# fadic.net
KiCad netlist of a schematic drawn in EAGLE
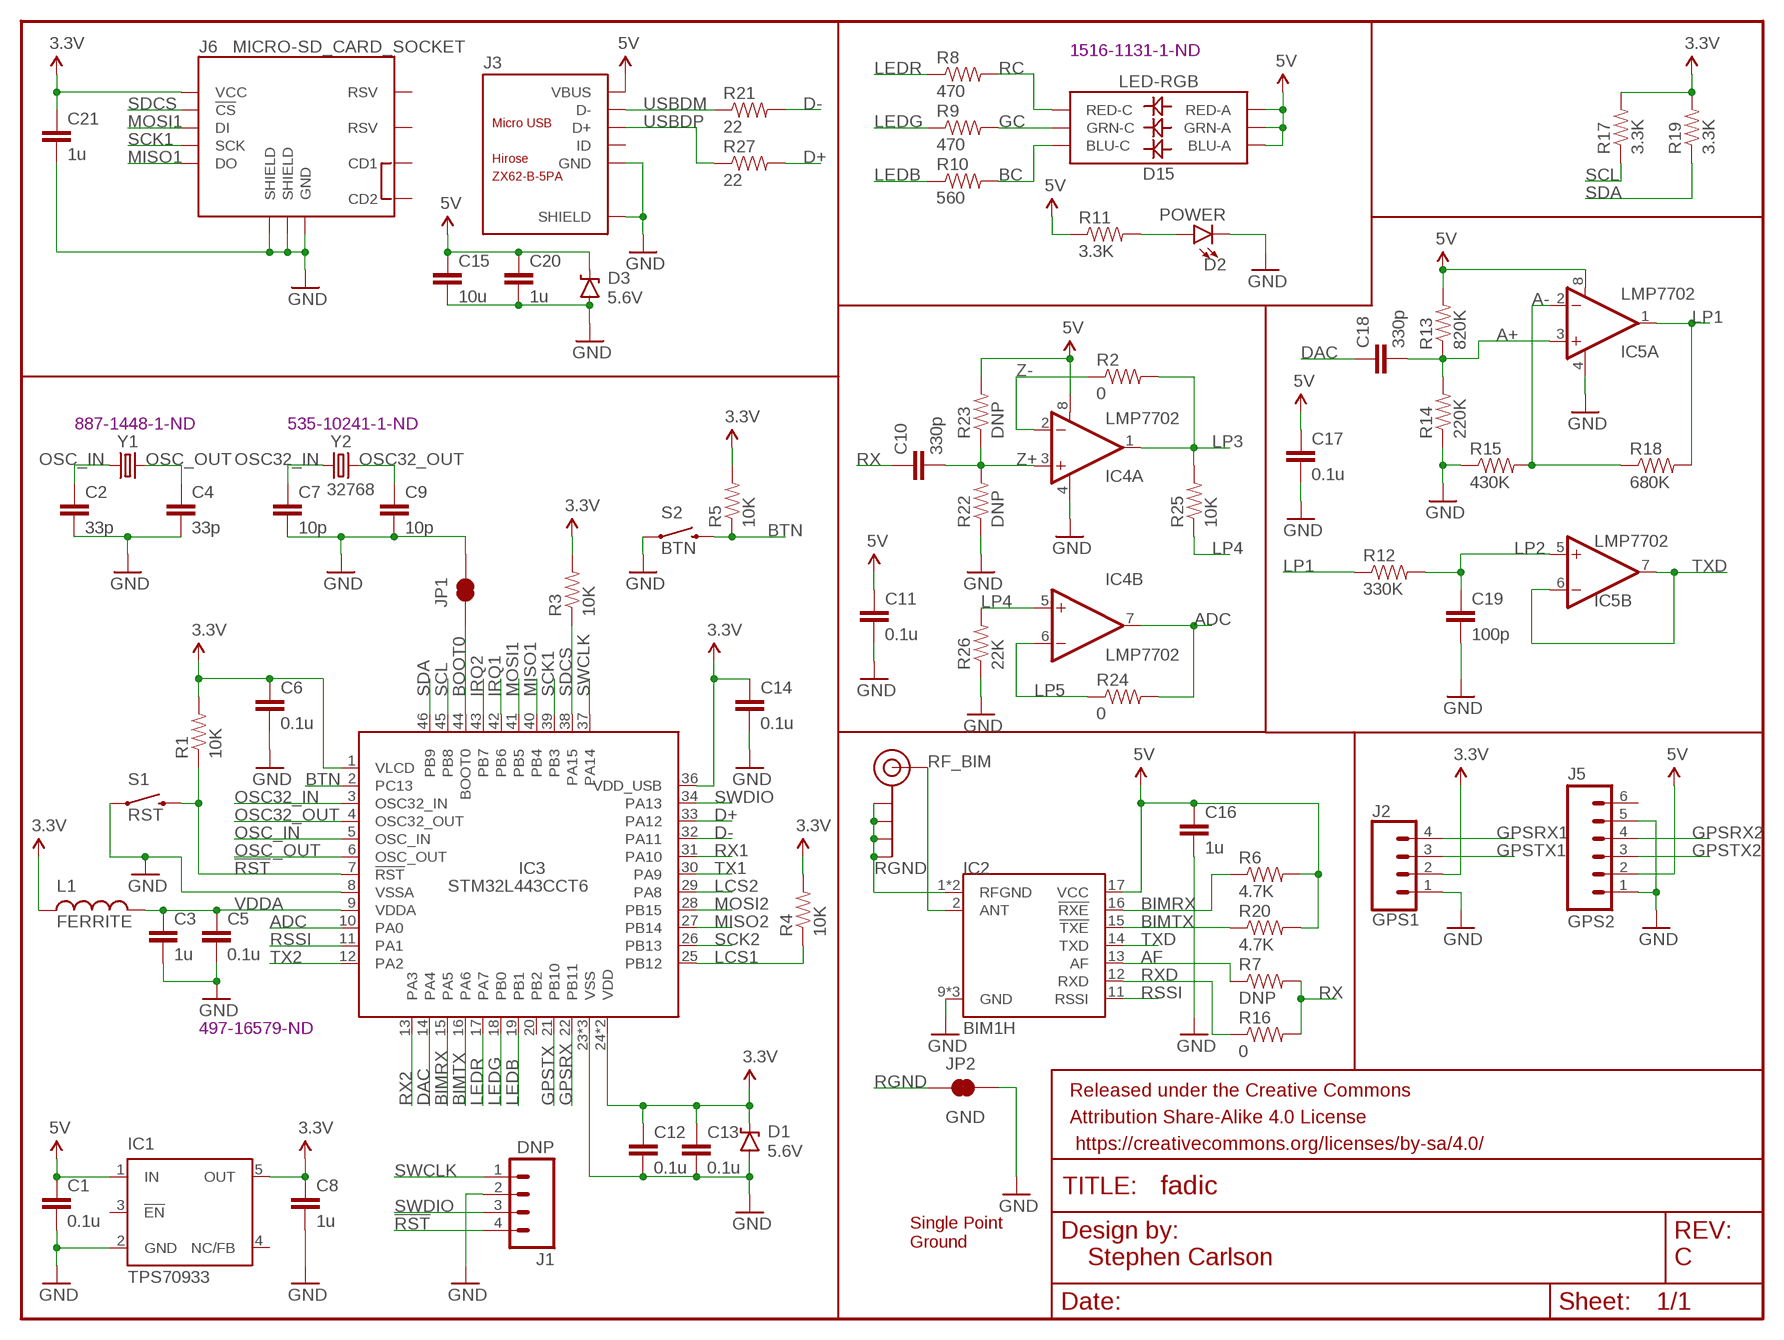
[diagram p0: schematic, sheet 1]

(export (version "E")
  (design (tool "Eeschema 10.0.6"))
  (components
    (comp (ref "C1")
      (value "0.1u")
      (footprint "eagle-import:0805")
      (libsource (lib "eagle-import") (part "CAP0805"))
    )
    (comp (ref "C2")
      (value "33p")
      (footprint "eagle-import:0805")
      (libsource (lib "eagle-import") (part "CAP0805"))
    )
    (comp (ref "C3")
      (value "1u")
      (footprint "eagle-import:0805")
      (libsource (lib "eagle-import") (part "CAP0805"))
    )
    (comp (ref "C4")
      (value "33p")
      (footprint "eagle-import:0805")
      (libsource (lib "eagle-import") (part "CAP0805"))
    )
    (comp (ref "C5")
      (value "0.1u")
      (footprint "eagle-import:0805")
      (libsource (lib "eagle-import") (part "CAP0805"))
    )
    (comp (ref "C6")
      (value "0.1u")
      (footprint "eagle-import:0805")
      (libsource (lib "eagle-import") (part "CAP0805"))
    )
    (comp (ref "C7")
      (value "10p")
      (footprint "eagle-import:0805")
      (libsource (lib "eagle-import") (part "CAP0805"))
    )
    (comp (ref "C8")
      (value "1u")
      (footprint "eagle-import:0805")
      (libsource (lib "eagle-import") (part "CAP0805"))
    )
    (comp (ref "C9")
      (value "10p")
      (footprint "eagle-import:0805")
      (libsource (lib "eagle-import") (part "CAP0805"))
    )
    (comp (ref "C10")
      (value "330p")
      (footprint "eagle-import:0805")
      (libsource (lib "eagle-import") (part "CAP0805"))
    )
    (comp (ref "C11")
      (value "0.1u")
      (footprint "eagle-import:0805")
      (libsource (lib "eagle-import") (part "CAP0805"))
    )
    (comp (ref "C12")
      (value "0.1u")
      (footprint "eagle-import:0805")
      (libsource (lib "eagle-import") (part "CAP0805"))
    )
    (comp (ref "C13")
      (value "0.1u")
      (footprint "eagle-import:0805")
      (libsource (lib "eagle-import") (part "CAP0805"))
    )
    (comp (ref "C14")
      (value "0.1u")
      (footprint "eagle-import:0805")
      (libsource (lib "eagle-import") (part "CAP0805"))
    )
    (comp (ref "C15")
      (value "10u")
      (footprint "eagle-import:0805")
      (libsource (lib "eagle-import") (part "CAP0805"))
    )
    (comp (ref "C16")
      (value "1u")
      (footprint "eagle-import:0805")
      (libsource (lib "eagle-import") (part "CAP0805"))
    )
    (comp (ref "C17")
      (value "0.1u")
      (footprint "eagle-import:0805")
      (libsource (lib "eagle-import") (part "CAP0805"))
    )
    (comp (ref "C18")
      (value "330p")
      (footprint "eagle-import:0805")
      (libsource (lib "eagle-import") (part "CAP0805"))
    )
    (comp (ref "C19")
      (value "100p")
      (footprint "eagle-import:0805")
      (libsource (lib "eagle-import") (part "CAP0805"))
    )
    (comp (ref "C20")
      (value "1u")
      (footprint "eagle-import:0805")
      (libsource (lib "eagle-import") (part "CAP0805"))
    )
    (comp (ref "C21")
      (value "1u")
      (footprint "eagle-import:0805")
      (libsource (lib "eagle-import") (part "CAP0805"))
    )
    (comp (ref "D1")
      (value "5.6V")
      (footprint "eagle-import:SOD-323")
      (libsource (lib "eagle-import") (part "DIODE-ZENER5.6V"))
    )
    (comp (ref "D2")
      (value "POWER")
      (footprint "eagle-import:LED-0603")
      (libsource (lib "eagle-import") (part "LED-GREEN0603"))
    )
    (comp (ref "D3")
      (value "5.6V")
      (footprint "eagle-import:SOD-323")
      (libsource (lib "eagle-import") (part "DIODE-ZENER5.6V"))
    )
    (comp (ref "D15")
      (value "LED-RGB")
      (footprint "eagle-import:LED-TRICOLOR-5050")
      (libsource (lib "eagle-import") (part "LED-RGB"))
    )
    (comp (ref "FRAME1")
      (value "FRAME-LETTERNO_PACKAGE")
      (footprint "eagle-import:DUMMY")
      (fields (field (name "DESIGNER") "Nobody"))
      (libsource (lib "eagle-import") (part "FRAME-LETTERNO_PACKAGE"))
    )
    (comp (ref "IC1")
      (value "TPS70933")
      (footprint "eagle-import:SOT23-DBV")
      (fields (field (name "MF") "TEXAS INSTRUMENTS") (field (name "MPN") "TPS77033DBVT"))
      (libsource (lib "eagle-import") (part "TPS77033"))
    )
    (comp (ref "IC2")
      (value "BIM1H")
      (footprint "eagle-import:BIM1H")
      (libsource (lib "eagle-import") (part "BIM1H"))
    )
    (comp (ref "IC3")
      (value "STM32L443CCT6")
      (footprint "eagle-import:TQFP48")
      (libsource (lib "eagle-import") (part "STM32L07C"))
    )
    (comp (ref "IC4")
      (value "LMP7702")
      (footprint "eagle-import:VSSOP8")
      (libsource (lib "eagle-import") (part "LMP7702VSSOP"))
    )
    (comp (ref "IC5")
      (value "LMP7702")
      (footprint "eagle-import:VSSOP8")
      (libsource (lib "eagle-import") (part "LMP7702VSSOP"))
    )
    (comp (ref "J$1")
      (value "SMA_EDGE")
      (footprint "eagle-import:SMA-EDGE")
      (libsource (lib "eagle-import") (part "SMA_EDGE"))
    )
    (comp (ref "J1")
      (value "DNP")
      (footprint "eagle-import:1X04_LOCK@1")
      (libsource (lib "eagle-import") (part "M04LOCK"))
    )
    (comp (ref "J2")
      (value "GPS1")
      (footprint "eagle-import:JST-4-PTH")
      (libsource (lib "eagle-import") (part "CONN_04JST-PTH"))
    )
    (comp (ref "J3")
      (value "ZX62-B-5PA")
      (footprint "eagle-import:MICRO-USB5+6P-SMD-0.65-AB")
      (libsource (lib "eagle-import") (part "MICRO-USB-SMD(ZX62-B-5PA)"))
    )
    (comp (ref "J5")
      (value "GPS2")
      (footprint "eagle-import:1X06-1MM")
      (libsource (lib "eagle-import") (part "M06SMD-1MM"))
    )
    (comp (ref "J6")
      (value "MICRO-SD_CARD_SOCKET")
      (footprint "eagle-import:MICRO-SD-SOCKET")
      (libsource (lib "eagle-import") (part "MICRO-SD_CARD_SOCKET"))
    )
    (comp (ref "JP1")
      (value "JUMPER-SMT_2_NC_TRACE_NO-SILK")
      (footprint "eagle-import:SMT-JUMPER_2_NC_TRACE_NO-SILK")
      (libsource (lib "eagle-import") (part "JUMPER-SMT_2_NC_TRACE_NO-SILK"))
    )
    (comp (ref "JP2")
      (value "GND")
      (footprint "eagle-import:PAD-JUMPER-2-NC_BY_TRACE_YES_SILK")
      (libsource (lib "eagle-import") (part "JUMPER-PAD-2-NC_BY_TRACE"))
    )
    (comp (ref "L1")
      (value "FERRITE")
      (footprint "eagle-import:0805")
      (libsource (lib "eagle-import") (part "INDUCTOR0805"))
    )
    (comp (ref "R1")
      (value "10K")
      (footprint "eagle-import:0805")
      (libsource (lib "eagle-import") (part "RESISTOR0805-RES"))
    )
    (comp (ref "R2")
      (value "0")
      (footprint "eagle-import:0805")
      (libsource (lib "eagle-import") (part "RESISTOR0805-RES"))
    )
    (comp (ref "R3")
      (value "10K")
      (footprint "eagle-import:0805")
      (libsource (lib "eagle-import") (part "RESISTOR0805-RES"))
    )
    (comp (ref "R4")
      (value "10K")
      (footprint "eagle-import:0805")
      (libsource (lib "eagle-import") (part "RESISTOR0805-RES"))
    )
    (comp (ref "R5")
      (value "10K")
      (footprint "eagle-import:0805")
      (libsource (lib "eagle-import") (part "RESISTOR0805-RES"))
    )
    (comp (ref "R6")
      (value "4.7K")
      (footprint "eagle-import:0805")
      (libsource (lib "eagle-import") (part "RESISTOR0805-RES"))
    )
    (comp (ref "R7")
      (value "DNP")
      (footprint "eagle-import:0805")
      (libsource (lib "eagle-import") (part "RESISTOR0805-RES"))
    )
    (comp (ref "R8")
      (value "470")
      (footprint "eagle-import:0805")
      (libsource (lib "eagle-import") (part "RESISTOR0805-RES"))
    )
    (comp (ref "R9")
      (value "470")
      (footprint "eagle-import:0805")
      (libsource (lib "eagle-import") (part "RESISTOR0805-RES"))
    )
    (comp (ref "R10")
      (value "560")
      (footprint "eagle-import:0805")
      (libsource (lib "eagle-import") (part "RESISTOR0805-RES"))
    )
    (comp (ref "R11")
      (value "3.3K")
      (footprint "eagle-import:0805")
      (libsource (lib "eagle-import") (part "RESISTOR0805-RES"))
    )
    (comp (ref "R12")
      (value "330K")
      (footprint "eagle-import:0805")
      (libsource (lib "eagle-import") (part "RESISTOR0805-RES"))
    )
    (comp (ref "R13")
      (value "820K")
      (footprint "eagle-import:0805")
      (libsource (lib "eagle-import") (part "RESISTOR0805-RES"))
    )
    (comp (ref "R14")
      (value "220K")
      (footprint "eagle-import:0805")
      (libsource (lib "eagle-import") (part "RESISTOR0805-RES"))
    )
    (comp (ref "R15")
      (value "430K")
      (footprint "eagle-import:0805")
      (libsource (lib "eagle-import") (part "RESISTOR0805-RES"))
    )
    (comp (ref "R16")
      (value "0")
      (footprint "eagle-import:0805")
      (libsource (lib "eagle-import") (part "RESISTOR0805-RES"))
    )
    (comp (ref "R17")
      (value "3.3K")
      (footprint "eagle-import:0805")
      (libsource (lib "eagle-import") (part "RESISTOR0805-RES"))
    )
    (comp (ref "R18")
      (value "680K")
      (footprint "eagle-import:0805")
      (libsource (lib "eagle-import") (part "RESISTOR0805-RES"))
    )
    (comp (ref "R19")
      (value "3.3K")
      (footprint "eagle-import:0805")
      (libsource (lib "eagle-import") (part "RESISTOR0805-RES"))
    )
    (comp (ref "R20")
      (value "4.7K")
      (footprint "eagle-import:0805")
      (libsource (lib "eagle-import") (part "RESISTOR0805-RES"))
    )
    (comp (ref "R21")
      (value "22")
      (footprint "eagle-import:0805")
      (libsource (lib "eagle-import") (part "RESISTOR0805-RES"))
    )
    (comp (ref "R22")
      (value "DNP")
      (footprint "eagle-import:0805")
      (libsource (lib "eagle-import") (part "RESISTOR0805-RES"))
    )
    (comp (ref "R23")
      (value "DNP")
      (footprint "eagle-import:0805")
      (libsource (lib "eagle-import") (part "RESISTOR0805-RES"))
    )
    (comp (ref "R24")
      (value "0")
      (footprint "eagle-import:0805")
      (libsource (lib "eagle-import") (part "RESISTOR0805-RES"))
    )
    (comp (ref "R25")
      (value "10K")
      (footprint "eagle-import:0805")
      (libsource (lib "eagle-import") (part "RESISTOR0805-RES"))
    )
    (comp (ref "R26")
      (value "22K")
      (footprint "eagle-import:0805")
      (libsource (lib "eagle-import") (part "RESISTOR0805-RES"))
    )
    (comp (ref "R27")
      (value "22")
      (footprint "eagle-import:0805")
      (libsource (lib "eagle-import") (part "RESISTOR0805-RES"))
    )
    (comp (ref "S1")
      (value "RST")
      (footprint "eagle-import:TACTILE-PTH-THIN")
      (libsource (lib "eagle-import") (part "SWITCH"))
    )
    (comp (ref "S2")
      (value "BTN")
      (footprint "eagle-import:TACTILE-PTH-THIN")
      (libsource (lib "eagle-import") (part "SWITCH"))
    )
    (comp (ref "Y1")
      (value "8M")
      (footprint "eagle-import:CRYSTAL-TXC-7A")
      (libsource (lib "eagle-import") (part "CRYSTALTXC-7A"))
    )
    (comp (ref "Y2")
      (value "32768")
      (footprint "eagle-import:ABS25")
      (libsource (lib "eagle-import") (part "CRYSTAL"))
    )
  )
  (nets
    (net (code "1") (name "/A+") (class "Default")
      (node (ref "C18") (pin "2") (pinfunction "2_2") (pintype "passive"))
      (node (ref "IC5") (pin "3") (pinfunction "+IN_3") (pintype "input"))
      (node (ref "R13") (pin "1") (pinfunction "1_1") (pintype "passive"))
      (node (ref "R14") (pin "2") (pinfunction "2_2") (pintype "passive"))
    )
    (net (code "2") (name "/A-") (class "Default")
      (node (ref "IC5") (pin "2") (pinfunction "-IN_2") (pintype "input"))
      (node (ref "R15") (pin "2") (pinfunction "2_2") (pintype "passive"))
      (node (ref "R18") (pin "1") (pinfunction "1_1") (pintype "passive"))
    )
    (net (code "3") (name "/ADC") (class "Default")
      (node (ref "IC3") (pin "10") (pinfunction "PA0_10") (pintype "bidirectional"))
      (node (ref "IC4") (pin "7") (pinfunction "OUT_7") (pintype "output"))
      (node (ref "R24") (pin "2") (pinfunction "2_2") (pintype "passive"))
    )
    (net (code "4") (name "/AF") (class "Default")
      (node (ref "IC2") (pin "13") (pinfunction "AF_13") (pintype "output"))
      (node (ref "R7") (pin "1") (pinfunction "1_1") (pintype "passive"))
    )
    (net (code "5") (name "/BC") (class "Default")
      (node (ref "D15") (pin "1") (pinfunction "BLU-C_1") (pintype "bidirectional"))
      (node (ref "R10") (pin "2") (pinfunction "2_2") (pintype "passive"))
    )
    (net (code "6") (name "/BIMRX") (class "Default")
      (node (ref "IC2") (pin "16") (pinfunction "~{RXE}_16") (pintype "open_collector"))
      (node (ref "IC3") (pin "15") (pinfunction "PA5_15") (pintype "bidirectional"))
      (node (ref "R6") (pin "1") (pinfunction "1_1") (pintype "passive"))
    )
    (net (code "7") (name "/BIMTX") (class "Default")
      (node (ref "IC2") (pin "15") (pinfunction "~{TXE}_15") (pintype "open_collector"))
      (node (ref "IC3") (pin "16") (pinfunction "PA6_16") (pintype "bidirectional"))
      (node (ref "R20") (pin "1") (pinfunction "1_1") (pintype "passive"))
    )
    (net (code "8") (name "/BOOT0") (class "Default")
      (node (ref "IC3") (pin "44") (pinfunction "BOOT0_44") (pintype "input"))
      (node (ref "JP1") (pin "1") (pinfunction "1_1") (pintype "passive"))
    )
    (net (code "9") (name "/BTN") (class "Default")
      (node (ref "IC3") (pin "2") (pinfunction "PC13_2") (pintype "bidirectional"))
      (node (ref "R5") (pin "1") (pinfunction "1_1") (pintype "passive"))
      (node (ref "S2") (pin "2") (pinfunction "2_2") (pintype "passive"))
    )
    (net (code "10") (name "/D+") (class "Default")
      (node (ref "IC3") (pin "33") (pinfunction "PA12_33") (pintype "bidirectional"))
      (node (ref "R27") (pin "2") (pinfunction "2_2") (pintype "passive"))
    )
    (net (code "11") (name "/D-") (class "Default")
      (node (ref "IC3") (pin "32") (pinfunction "PA11_32") (pintype "bidirectional"))
      (node (ref "R21") (pin "2") (pinfunction "2_2") (pintype "passive"))
    )
    (net (code "12") (name "/DAC") (class "Default")
      (node (ref "C18") (pin "1") (pinfunction "1_1") (pintype "passive"))
      (node (ref "IC3") (pin "14") (pinfunction "PA4_14") (pintype "bidirectional"))
    )
    (net (code "13") (name "/GC") (class "Default")
      (node (ref "D15") (pin "2") (pinfunction "GRN-C_2") (pintype "bidirectional"))
      (node (ref "R9") (pin "2") (pinfunction "2_2") (pintype "passive"))
    )
    (net (code "14") (name "/GPSRX") (class "Default")
      (node (ref "IC3") (pin "22") (pinfunction "PB11_22") (pintype "bidirectional"))
    )
    (net (code "15") (name "/GPSRX1") (class "Default")
      (node (ref "J2") (pin "4") (pinfunction "4_4") (pintype "passive"))
    )
    (net (code "16") (name "/GPSRX2") (class "Default")
      (node (ref "J5") (pin "4") (pinfunction "4_4") (pintype "passive"))
    )
    (net (code "17") (name "/GPSTX") (class "Default")
      (node (ref "IC3") (pin "21") (pinfunction "PB10_21") (pintype "bidirectional"))
    )
    (net (code "18") (name "/GPSTX1") (class "Default")
      (node (ref "J2") (pin "3") (pinfunction "3_3") (pintype "passive"))
    )
    (net (code "19") (name "/GPSTX2") (class "Default")
      (node (ref "J5") (pin "3") (pinfunction "3_3") (pintype "passive"))
    )
    (net (code "20") (name "/IRQ1") (class "Default")
      (node (ref "IC3") (pin "42") (pinfunction "PB6_42") (pintype "bidirectional"))
    )
    (net (code "21") (name "/IRQ2") (class "Default")
      (node (ref "IC3") (pin "43") (pinfunction "PB7_43") (pintype "bidirectional"))
    )
    (net (code "22") (name "/LCS1") (class "Default")
      (node (ref "IC3") (pin "25") (pinfunction "PB12_25") (pintype "bidirectional"))
      (node (ref "R4") (pin "1") (pinfunction "1_1") (pintype "passive"))
    )
    (net (code "23") (name "/LCS2") (class "Default")
      (node (ref "IC3") (pin "29") (pinfunction "PA8_29") (pintype "bidirectional"))
    )
    (net (code "24") (name "/LEDB") (class "Default")
      (node (ref "IC3") (pin "19") (pinfunction "PB1_19") (pintype "bidirectional"))
      (node (ref "R10") (pin "1") (pinfunction "1_1") (pintype "passive"))
    )
    (net (code "25") (name "/LEDG") (class "Default")
      (node (ref "IC3") (pin "18") (pinfunction "PB0_18") (pintype "bidirectional"))
      (node (ref "R9") (pin "1") (pinfunction "1_1") (pintype "passive"))
    )
    (net (code "26") (name "/LEDR") (class "Default")
      (node (ref "IC3") (pin "17") (pinfunction "PA7_17") (pintype "bidirectional"))
      (node (ref "R8") (pin "1") (pinfunction "1_1") (pintype "passive"))
    )
    (net (code "27") (name "/LP1") (class "Default")
      (node (ref "IC5") (pin "1") (pinfunction "OUT_1") (pintype "output"))
      (node (ref "R12") (pin "1") (pinfunction "1_1") (pintype "passive"))
      (node (ref "R18") (pin "2") (pinfunction "2_2") (pintype "passive"))
    )
    (net (code "28") (name "/LP2") (class "Default")
      (node (ref "C19") (pin "1") (pinfunction "1_1") (pintype "passive"))
      (node (ref "IC5") (pin "5") (pinfunction "+IN_5") (pintype "input"))
      (node (ref "R12") (pin "2") (pinfunction "2_2") (pintype "passive"))
    )
    (net (code "29") (name "/LP3") (class "Default")
      (node (ref "IC4") (pin "1") (pinfunction "OUT_1") (pintype "output"))
      (node (ref "R2") (pin "2") (pinfunction "2_2") (pintype "passive"))
      (node (ref "R25") (pin "2") (pinfunction "2_2") (pintype "passive"))
    )
    (net (code "30") (name "/LP4") (class "Default")
      (node (ref "IC4") (pin "5") (pinfunction "+IN_5") (pintype "input"))
      (node (ref "R25") (pin "1") (pinfunction "1_1") (pintype "passive"))
      (node (ref "R26") (pin "2") (pinfunction "2_2") (pintype "passive"))
    )
    (net (code "31") (name "/LP5") (class "Default")
      (node (ref "IC4") (pin "6") (pinfunction "-IN_6") (pintype "input"))
      (node (ref "R24") (pin "1") (pinfunction "1_1") (pintype "passive"))
    )
    (net (code "32") (name "/MISO1") (class "Default")
      (node (ref "IC3") (pin "40") (pinfunction "PB4_40") (pintype "bidirectional"))
      (node (ref "J6") (pin "DO") (pinfunction "DO_DO") (pintype "bidirectional"))
    )
    (net (code "33") (name "/MISO2") (class "Default")
      (node (ref "IC3") (pin "27") (pinfunction "PB14_27") (pintype "bidirectional"))
    )
    (net (code "34") (name "/MOSI1") (class "Default")
      (node (ref "IC3") (pin "41") (pinfunction "PB5_41") (pintype "bidirectional"))
      (node (ref "J6") (pin "DI") (pinfunction "DI_DI") (pintype "bidirectional"))
    )
    (net (code "35") (name "/MOSI2") (class "Default")
      (node (ref "IC3") (pin "28") (pinfunction "PB15_28") (pintype "bidirectional"))
    )
    (net (code "36") (name "/OSC32_IN") (class "Default")
      (node (ref "C7") (pin "1") (pinfunction "1_1") (pintype "passive"))
      (node (ref "IC3") (pin "3") (pinfunction "OSC32_IN_3") (pintype "bidirectional"))
      (node (ref "Y2") (pin "1") (pinfunction "1_1") (pintype "passive"))
    )
    (net (code "37") (name "/OSC32_OUT") (class "Default")
      (node (ref "C9") (pin "1") (pinfunction "1_1") (pintype "passive"))
      (node (ref "IC3") (pin "4") (pinfunction "OSC32_OUT_4") (pintype "bidirectional"))
      (node (ref "Y2") (pin "4") (pinfunction "2_4") (pintype "passive"))
    )
    (net (code "38") (name "/OSC_IN") (class "Default")
      (node (ref "C2") (pin "1") (pinfunction "1_1") (pintype "passive"))
      (node (ref "IC3") (pin "5") (pinfunction "OSC_IN_5") (pintype "bidirectional"))
      (node (ref "Y1") (pin "P$1") (pinfunction "1_P$1") (pintype "passive"))
    )
    (net (code "39") (name "/OSC_OUT") (class "Default")
      (node (ref "C4") (pin "1") (pinfunction "1_1") (pintype "passive"))
      (node (ref "IC3") (pin "6") (pinfunction "OSC_OUT_6") (pintype "bidirectional"))
      (node (ref "Y1") (pin "P$2") (pinfunction "2_P$2") (pintype "passive"))
    )
    (net (code "40") (name "/RC") (class "Default")
      (node (ref "D15") (pin "3") (pinfunction "RED-C_3") (pintype "bidirectional"))
      (node (ref "R8") (pin "2") (pinfunction "2_2") (pintype "passive"))
    )
    (net (code "41") (name "/RF_BIM") (class "Default")
      (node (ref "IC2") (pin "2") (pinfunction "ANT_2") (pintype "passive"))
      (node (ref "J$1") (pin "SIG") (pinfunction "SIGNAL_SIG") (pintype "bidirectional"))
    )
    (net (code "42") (name "/RGND") (class "Default")
      (node (ref "IC2") (pin "1") (pinfunction "RFGND_1") (pintype "power_in"))
      (node (ref "IC2") (pin "3") (pinfunction "RFGND_3") (pintype "power_in"))
      (node (ref "J$1") (pin "GND@0") (pinfunction "GND_GND@0") (pintype "bidirectional"))
      (node (ref "J$1") (pin "GND@1") (pinfunction "GND_GND@1") (pintype "bidirectional"))
      (node (ref "J$1") (pin "GND@2") (pinfunction "GND_GND@2") (pintype "bidirectional"))
      (node (ref "J$1") (pin "GND@3") (pinfunction "GND_GND@3") (pintype "bidirectional"))
      (node (ref "JP2") (pin "1") (pinfunction "1_1") (pintype "passive"))
    )
    (net (code "43") (name "/RSSI") (class "Default")
      (node (ref "IC2") (pin "11") (pinfunction "RSSI_11") (pintype "output"))
      (node (ref "IC3") (pin "11") (pinfunction "PA1_11") (pintype "bidirectional"))
    )
    (net (code "44") (name "/RX") (class "Default")
      (node (ref "C10") (pin "1") (pinfunction "1_1") (pintype "passive"))
      (node (ref "R16") (pin "2") (pinfunction "2_2") (pintype "passive"))
      (node (ref "R7") (pin "2") (pinfunction "2_2") (pintype "passive"))
    )
    (net (code "45") (name "/RX1") (class "Default")
      (node (ref "IC3") (pin "31") (pinfunction "PA10_31") (pintype "bidirectional"))
    )
    (net (code "46") (name "/RX2") (class "Default")
      (node (ref "IC3") (pin "13") (pinfunction "PA3_13") (pintype "bidirectional"))
    )
    (net (code "47") (name "/RXD") (class "Default")
      (node (ref "IC2") (pin "12") (pinfunction "RXD_12") (pintype "output"))
      (node (ref "R16") (pin "1") (pinfunction "1_1") (pintype "passive"))
    )
    (net (code "48") (name "/SCK1") (class "Default")
      (node (ref "IC3") (pin "39") (pinfunction "PB3_39") (pintype "bidirectional"))
      (node (ref "J6") (pin "SCLK") (pinfunction "SCK_SCLK") (pintype "bidirectional"))
    )
    (net (code "49") (name "/SCK2") (class "Default")
      (node (ref "IC3") (pin "26") (pinfunction "PB13_26") (pintype "bidirectional"))
    )
    (net (code "50") (name "/SCL") (class "Default")
      (node (ref "IC3") (pin "45") (pinfunction "PB8_45") (pintype "bidirectional"))
      (node (ref "R17") (pin "1") (pinfunction "1_1") (pintype "passive"))
    )
    (net (code "51") (name "/SDA") (class "Default")
      (node (ref "IC3") (pin "46") (pinfunction "PB9_46") (pintype "bidirectional"))
      (node (ref "R19") (pin "1") (pinfunction "1_1") (pintype "passive"))
    )
    (net (code "52") (name "/SDCS") (class "Default")
      (node (ref "IC3") (pin "38") (pinfunction "PA15_38") (pintype "bidirectional"))
      (node (ref "J6") (pin "CS") (pinfunction "~{CS}_CS") (pintype "bidirectional"))
      (node (ref "R3") (pin "1") (pinfunction "1_1") (pintype "passive"))
    )
    (net (code "53") (name "/SWCLK") (class "Default")
      (node (ref "IC3") (pin "37") (pinfunction "PA14_37") (pintype "bidirectional"))
      (node (ref "J1") (pin "1") (pinfunction "1_1") (pintype "passive"))
    )
    (net (code "54") (name "/SWDIO") (class "Default")
      (node (ref "IC3") (pin "34") (pinfunction "PA13_34") (pintype "bidirectional"))
      (node (ref "J1") (pin "3") (pinfunction "3_3") (pintype "passive"))
    )
    (net (code "55") (name "/TX1") (class "Default")
      (node (ref "IC3") (pin "30") (pinfunction "PA9_30") (pintype "bidirectional"))
    )
    (net (code "56") (name "/TX2") (class "Default")
      (node (ref "IC3") (pin "12") (pinfunction "PA2_12") (pintype "bidirectional"))
    )
    (net (code "57") (name "/TXD") (class "Default")
      (node (ref "IC2") (pin "14") (pinfunction "TXD_14") (pintype "input"))
      (node (ref "IC5") (pin "6") (pinfunction "-IN_6") (pintype "input"))
      (node (ref "IC5") (pin "7") (pinfunction "OUT_7") (pintype "output"))
    )
    (net (code "58") (name "/USBDM") (class "Default")
      (node (ref "J3") (pin "2") (pinfunction "D-_2") (pintype "bidirectional"))
      (node (ref "R21") (pin "1") (pinfunction "1_1") (pintype "passive"))
    )
    (net (code "59") (name "/USBDP") (class "Default")
      (node (ref "J3") (pin "3") (pinfunction "D+_3") (pintype "bidirectional"))
      (node (ref "R27") (pin "1") (pinfunction "1_1") (pintype "passive"))
    )
    (net (code "60") (name "/VDDA") (class "Default")
      (node (ref "C3") (pin "1") (pinfunction "1_1") (pintype "passive"))
      (node (ref "C5") (pin "1") (pinfunction "1_1") (pintype "passive"))
      (node (ref "IC3") (pin "9") (pinfunction "VDDA_9") (pintype "power_in"))
      (node (ref "L1") (pin "2") (pinfunction "2_2") (pintype "passive"))
    )
    (net (code "61") (name "/Z+") (class "Default")
      (node (ref "C10") (pin "2") (pinfunction "2_2") (pintype "passive"))
      (node (ref "IC4") (pin "3") (pinfunction "+IN_3") (pintype "input"))
      (node (ref "R22") (pin "2") (pinfunction "2_2") (pintype "passive"))
      (node (ref "R23") (pin "1") (pinfunction "1_1") (pintype "passive"))
    )
    (net (code "62") (name "/Z-") (class "Default")
      (node (ref "IC4") (pin "2") (pinfunction "-IN_2") (pintype "input"))
      (node (ref "R2") (pin "1") (pinfunction "1_1") (pintype "passive"))
    )
    (net (code "63") (name "/~{RST}") (class "Default")
      (node (ref "IC3") (pin "7") (pinfunction "~{RST}_7") (pintype "input"))
      (node (ref "J1") (pin "4") (pinfunction "4_4") (pintype "passive"))
      (node (ref "R1") (pin "1") (pinfunction "1_1") (pintype "passive"))
      (node (ref "S1") (pin "2") (pinfunction "2_2") (pintype "passive"))
    )
    (net (code "64") (name "3.3V") (class "Default")
      (node (ref "C12") (pin "1") (pinfunction "1_1") (pintype "passive"))
      (node (ref "C13") (pin "1") (pinfunction "1_1") (pintype "passive"))
      (node (ref "C14") (pin "1") (pinfunction "1_1") (pintype "passive"))
      (node (ref "C21") (pin "1") (pinfunction "1_1") (pintype "passive"))
      (node (ref "C6") (pin "1") (pinfunction "1_1") (pintype "passive"))
      (node (ref "C8") (pin "1") (pinfunction "1_1") (pintype "passive"))
      (node (ref "D1") (pin "C") (pinfunction "C_C") (pintype "passive"))
      (node (ref "IC1") (pin "5") (pinfunction "OUT_5") (pintype "passive"))
      (node (ref "IC3") (pin "1") (pinfunction "VLCD_1") (pintype "power_in"))
      (node (ref "IC3") (pin "24") (pinfunction "VDD_24") (pintype "power_in"))
      (node (ref "IC3") (pin "36") (pinfunction "VDD_USB_36") (pintype "power_in"))
      (node (ref "IC3") (pin "48") (pinfunction "VDD_48") (pintype "power_in"))
      (node (ref "J2") (pin "2") (pinfunction "2_2") (pintype "passive"))
      (node (ref "J6") (pin "VCC") (pinfunction "VCC_VCC") (pintype "bidirectional"))
      (node (ref "L1") (pin "1") (pinfunction "1_1") (pintype "passive"))
      (node (ref "R1") (pin "2") (pinfunction "2_2") (pintype "passive"))
      (node (ref "R17") (pin "2") (pinfunction "2_2") (pintype "passive"))
      (node (ref "R19") (pin "2") (pinfunction "2_2") (pintype "passive"))
      (node (ref "R3") (pin "2") (pinfunction "2_2") (pintype "passive"))
      (node (ref "R4") (pin "2") (pinfunction "2_2") (pintype "passive"))
      (node (ref "R5") (pin "2") (pinfunction "2_2") (pintype "passive"))
    )
    (net (code "65") (name "5V") (class "Default")
      (node (ref "C1") (pin "1") (pinfunction "1_1") (pintype "passive"))
      (node (ref "C11") (pin "1") (pinfunction "1_1") (pintype "passive"))
      (node (ref "C15") (pin "1") (pinfunction "1_1") (pintype "passive"))
      (node (ref "C16") (pin "1") (pinfunction "1_1") (pintype "passive"))
      (node (ref "C17") (pin "1") (pinfunction "1_1") (pintype "passive"))
      (node (ref "C20") (pin "1") (pinfunction "1_1") (pintype "passive"))
      (node (ref "D15") (pin "4") (pinfunction "RED-A_4") (pintype "bidirectional"))
      (node (ref "D15") (pin "5") (pinfunction "GRN-A_5") (pintype "bidirectional"))
      (node (ref "D15") (pin "6") (pinfunction "BLU-A_6") (pintype "bidirectional"))
      (node (ref "D3") (pin "C") (pinfunction "C_C") (pintype "passive"))
      (node (ref "IC1") (pin "1") (pinfunction "IN_1") (pintype "input"))
      (node (ref "IC2") (pin "17") (pinfunction "VCC_17") (pintype "power_in"))
      (node (ref "IC4") (pin "8") (pinfunction "V+_8") (pintype "power_in"))
      (node (ref "IC5") (pin "8") (pinfunction "V+_8") (pintype "power_in"))
      (node (ref "J3") (pin "1") (pinfunction "VBUS_1") (pintype "power_in"))
      (node (ref "J5") (pin "2") (pinfunction "2_2") (pintype "passive"))
      (node (ref "R11") (pin "1") (pinfunction "1_1") (pintype "passive"))
      (node (ref "R13") (pin "2") (pinfunction "2_2") (pintype "passive"))
      (node (ref "R20") (pin "2") (pinfunction "2_2") (pintype "passive"))
      (node (ref "R23") (pin "2") (pinfunction "2_2") (pintype "passive"))
      (node (ref "R6") (pin "2") (pinfunction "2_2") (pintype "passive"))
    )
    (net (code "66") (name "GND") (class "Default")
      (node (ref "C1") (pin "2") (pinfunction "2_2") (pintype "passive"))
      (node (ref "C11") (pin "2") (pinfunction "2_2") (pintype "passive"))
      (node (ref "C12") (pin "2") (pinfunction "2_2") (pintype "passive"))
      (node (ref "C13") (pin "2") (pinfunction "2_2") (pintype "passive"))
      (node (ref "C14") (pin "2") (pinfunction "2_2") (pintype "passive"))
      (node (ref "C15") (pin "2") (pinfunction "2_2") (pintype "passive"))
      (node (ref "C16") (pin "2") (pinfunction "2_2") (pintype "passive"))
      (node (ref "C17") (pin "2") (pinfunction "2_2") (pintype "passive"))
      (node (ref "C19") (pin "2") (pinfunction "2_2") (pintype "passive"))
      (node (ref "C2") (pin "2") (pinfunction "2_2") (pintype "passive"))
      (node (ref "C20") (pin "2") (pinfunction "2_2") (pintype "passive"))
      (node (ref "C21") (pin "2") (pinfunction "2_2") (pintype "passive"))
      (node (ref "C3") (pin "2") (pinfunction "2_2") (pintype "passive"))
      (node (ref "C4") (pin "2") (pinfunction "2_2") (pintype "passive"))
      (node (ref "C5") (pin "2") (pinfunction "2_2") (pintype "passive"))
      (node (ref "C6") (pin "2") (pinfunction "2_2") (pintype "passive"))
      (node (ref "C7") (pin "2") (pinfunction "2_2") (pintype "passive"))
      (node (ref "C8") (pin "2") (pinfunction "2_2") (pintype "passive"))
      (node (ref "C9") (pin "2") (pinfunction "2_2") (pintype "passive"))
      (node (ref "D1") (pin "A") (pinfunction "A_A") (pintype "passive"))
      (node (ref "D2") (pin "C") (pinfunction "C_C") (pintype "passive"))
      (node (ref "D3") (pin "A") (pinfunction "A_A") (pintype "passive"))
      (node (ref "IC1") (pin "2") (pinfunction "GND_2") (pintype "power_in"))
      (node (ref "IC2") (pin "10") (pinfunction "GND_10") (pintype "power_in"))
      (node (ref "IC2") (pin "18") (pinfunction "GND_18") (pintype "power_in"))
      (node (ref "IC2") (pin "9") (pinfunction "GND_9") (pintype "power_in"))
      (node (ref "IC3") (pin "23") (pinfunction "VSS_23") (pintype "power_in"))
      (node (ref "IC3") (pin "35") (pinfunction "VSS_35") (pintype "power_in"))
      (node (ref "IC3") (pin "47") (pinfunction "VSS_47") (pintype "power_in"))
      (node (ref "IC3") (pin "8") (pinfunction "VSSA_8") (pintype "power_in"))
      (node (ref "IC4") (pin "4") (pinfunction "V-_4") (pintype "power_in"))
      (node (ref "IC5") (pin "4") (pinfunction "V-_4") (pintype "power_in"))
      (node (ref "J1") (pin "2") (pinfunction "2_2") (pintype "passive"))
      (node (ref "J2") (pin "1") (pinfunction "1_1") (pintype "passive"))
      (node (ref "J3") (pin "5") (pinfunction "GND_5") (pintype "power_in"))
      (node (ref "J3") (pin "P1") (pinfunction "SHIELD_P1") (pintype "power_in"))
      (node (ref "J3") (pin "P2") (pinfunction "SHIELD_P2") (pintype "power_in"))
      (node (ref "J3") (pin "P3") (pinfunction "SHIELD_P3") (pintype "power_in"))
      (node (ref "J3") (pin "P4") (pinfunction "SHIELD_P4") (pintype "power_in"))
      (node (ref "J3") (pin "P5") (pinfunction "SHIELD_P5") (pintype "power_in"))
      (node (ref "J3") (pin "P6") (pinfunction "SHIELD_P6") (pintype "power_in"))
      (node (ref "J5") (pin "1") (pinfunction "1_1") (pintype "passive"))
      (node (ref "J5") (pin "5") (pinfunction "5_5") (pintype "passive"))
      (node (ref "J6") (pin "GND") (pinfunction "GND_GND") (pintype "bidirectional"))
      (node (ref "J6") (pin "GND1") (pinfunction "SHIELD_GND1") (pintype "bidirectional"))
      (node (ref "J6") (pin "GND3") (pinfunction "SHIELD_GND3") (pintype "bidirectional"))
      (node (ref "JP1") (pin "2") (pinfunction "2_2") (pintype "passive"))
      (node (ref "JP2") (pin "2") (pinfunction "2_2") (pintype "passive"))
      (node (ref "R14") (pin "1") (pinfunction "1_1") (pintype "passive"))
      (node (ref "R15") (pin "1") (pinfunction "1_1") (pintype "passive"))
      (node (ref "R22") (pin "1") (pinfunction "1_1") (pintype "passive"))
      (node (ref "R26") (pin "1") (pinfunction "1_1") (pintype "passive"))
      (node (ref "S1") (pin "1") (pinfunction "1_1") (pintype "passive"))
      (node (ref "S2") (pin "1") (pinfunction "1_1") (pintype "passive"))
    )
    (net (code "67") (name "Net-(D2-PadA)") (class "Default")
      (node (ref "D2") (pin "A") (pinfunction "A_A") (pintype "passive"))
      (node (ref "R11") (pin "2") (pinfunction "2_2") (pintype "passive"))
    )
    (net (code "68") (name "unconnected-(IC1-NC{slash}FB-Pad4)") (class "Default")
      (node (ref "IC1") (pin "4") (pinfunction "NC/FB_4") (pintype "passive"))
    )
    (net (code "69") (name "unconnected-(IC1-~{EN}-Pad3)") (class "Default")
      (node (ref "IC1") (pin "3") (pinfunction "~{EN}_3") (pintype "input"))
    )
    (net (code "70") (name "unconnected-(IC3-PB2-Pad20)") (class "Default")
      (node (ref "IC3") (pin "20") (pinfunction "PB2_20") (pintype "bidirectional"))
    )
    (net (code "71") (name "unconnected-(J3-ID-Pad4)") (class "Default")
      (node (ref "J3") (pin "4") (pinfunction "ID_4") (pintype "bidirectional"))
    )
    (net (code "72") (name "unconnected-(J5-Pad6)") (class "Default")
      (node (ref "J5") (pin "6") (pinfunction "6_6") (pintype "passive"))
    )
    (net (code "73") (name "unconnected-(J6-PadCD1)") (class "Default")
      (node (ref "J6") (pin "CD1") (pinfunction "CD1_CD1") (pintype "bidirectional"))
    )
    (net (code "74") (name "unconnected-(J6-PadCD2)") (class "Default")
      (node (ref "J6") (pin "CD2") (pinfunction "CD2_CD2") (pintype "bidirectional"))
    )
    (net (code "75") (name "unconnected-(J6-RSV-PadRSV1)") (class "Default")
      (node (ref "J6") (pin "RSV1") (pinfunction "RSV_RSV1") (pintype "bidirectional"))
    )
    (net (code "76") (name "unconnected-(J6-RSV-PadRSV2)") (class "Default")
      (node (ref "J6") (pin "RSV2") (pinfunction "RSV_RSV2") (pintype "bidirectional"))
    )
  )
)
